# cooldrv.net
KiCad netlist of a schematic drawn in EAGLE
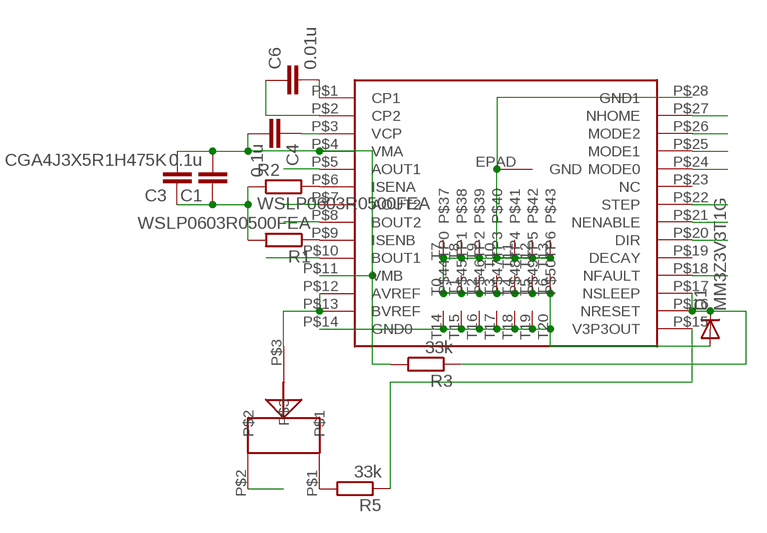
[diagram p0: schematic, sheet 1]

(export (version "E")
  (design (tool "Eeschema 10.0.6"))
  (components
    (comp (ref "C1")
      (value "0.1u")
      (footprint "eagle-import:C0603")
      (libsource (lib "eagle-import") (part "C-EUC0603"))
    )
    (comp (ref "C3")
      (value "CGA4J3X5R1H475K")
      (footprint "eagle-import:C0805K")
      (libsource (lib "eagle-import") (part "C-EUC0805K"))
    )
    (comp (ref "C4")
      (value "0.1u")
      (footprint "eagle-import:C0603K")
      (libsource (lib "eagle-import") (part "C-EUC0603K"))
    )
    (comp (ref "C6")
      (value "0.01u")
      (footprint "eagle-import:C0603")
      (libsource (lib "eagle-import") (part "C-EUC0603"))
    )
    (comp (ref "D1")
      (value "MM3Z3V3T1G")
      (footprint "eagle-import:SOD323-R")
      (libsource (lib "eagle-import") (part "DIODE-SOD323-R"))
    )
    (comp (ref "R1")
      (value "WSLP0603R0500FEA")
      (footprint "eagle-import:0805C")
      (libsource (lib "eagle-import") (part "0805CS"))
    )
    (comp (ref "R2")
      (value "WSLP0603R0500FEA")
      (footprint "eagle-import:0805C")
      (libsource (lib "eagle-import") (part "0805CS"))
    )
    (comp (ref "R3")
      (value "33k")
      (footprint "eagle-import:R0603")
      (libsource (lib "eagle-import") (part "R-EU_R0603"))
    )
    (comp (ref "R5")
      (value "33k")
      (footprint "eagle-import:R0603")
      (libsource (lib "eagle-import") (part "R-EU_R0603"))
    )
    (comp (ref "U$1")
      (value "DRV8825")
      (footprint "eagle-import:ETSSOP28")
      (libsource (lib "eagle-import") (part "DRV8825"))
    )
    (comp (ref "U$2")
      (value "EVM-3YSX50B14")
      (footprint "eagle-import:TRIMMER3MM")
      (libsource (lib "eagle-import") (part "TRIMMER3MM"))
    )
  )
  (nets
    (net (code "1") (name "/GND") (class "Default")
      (node (ref "C1") (pin "1") (pinfunction "1_1") (pintype "passive"))
      (node (ref "C3") (pin "1") (pinfunction "1_1") (pintype "passive"))
      (node (ref "D1") (pin "A") (pinfunction "A_A") (pintype "passive"))
      (node (ref "R1") (pin "2") (pinfunction "2_2") (pintype "passive"))
      (node (ref "R2") (pin "1") (pinfunction "1_1") (pintype "passive"))
      (node (ref "U$1") (pin "EPAD") (pinfunction "GND_EPAD") (pintype "bidirectional"))
      (node (ref "U$1") (pin "P$14") (pinfunction "GND0_P$14") (pintype "bidirectional"))
      (node (ref "U$1") (pin "P$28") (pinfunction "GND1_P$28") (pintype "bidirectional"))
      (node (ref "U$1") (pin "T0") (pinfunction "TP0_T0") (pintype "bidirectional"))
      (node (ref "U$1") (pin "T1") (pinfunction "TP1_T1") (pintype "bidirectional"))
      (node (ref "U$1") (pin "T10") (pinfunction "P$40_T10") (pintype "bidirectional"))
      (node (ref "U$1") (pin "T11") (pinfunction "P$41_T11") (pintype "bidirectional"))
      (node (ref "U$1") (pin "T12") (pinfunction "P$42_T12") (pintype "bidirectional"))
      (node (ref "U$1") (pin "T13") (pinfunction "P$43_T13") (pintype "bidirectional"))
      (node (ref "U$1") (pin "T14") (pinfunction "P$44_T14") (pintype "bidirectional"))
      (node (ref "U$1") (pin "T15") (pinfunction "P$45_T15") (pintype "bidirectional"))
      (node (ref "U$1") (pin "T16") (pinfunction "P$46_T16") (pintype "bidirectional"))
      (node (ref "U$1") (pin "T17") (pinfunction "P$47_T17") (pintype "bidirectional"))
      (node (ref "U$1") (pin "T18") (pinfunction "P$48_T18") (pintype "bidirectional"))
      (node (ref "U$1") (pin "T19") (pinfunction "P$49_T19") (pintype "bidirectional"))
      (node (ref "U$1") (pin "T2") (pinfunction "TP2_T2") (pintype "bidirectional"))
      (node (ref "U$1") (pin "T20") (pinfunction "P$50_T20") (pintype "bidirectional"))
      (node (ref "U$1") (pin "T3") (pinfunction "TP3_T3") (pintype "bidirectional"))
      (node (ref "U$1") (pin "T4") (pinfunction "TP4_T4") (pintype "bidirectional"))
      (node (ref "U$1") (pin "T5") (pinfunction "TP5_T5") (pintype "bidirectional"))
      (node (ref "U$1") (pin "T6") (pinfunction "TP6_T6") (pintype "bidirectional"))
      (node (ref "U$1") (pin "T7") (pinfunction "P$37_T7") (pintype "bidirectional"))
      (node (ref "U$1") (pin "T8") (pinfunction "P$38_T8") (pintype "bidirectional"))
      (node (ref "U$1") (pin "T9") (pinfunction "P$39_T9") (pintype "bidirectional"))
      (node (ref "U$2") (pin "P$2") (pinfunction "P$2_P$2") (pintype "bidirectional"))
    )
    (net (code "2") (name "Net-(R5-Pad2)") (class "Default")
      (node (ref "R5") (pin "2") (pinfunction "2_2") (pintype "passive"))
      (node (ref "U$2") (pin "P$1") (pinfunction "P$1_P$1") (pintype "bidirectional"))
    )
    (net (code "3") (name "Net-(U$1-AVREF)") (class "Default")
      (node (ref "U$1") (pin "P$12") (pinfunction "AVREF_P$12") (pintype "bidirectional"))
      (node (ref "U$1") (pin "P$13") (pinfunction "BVREF_P$13") (pintype "bidirectional"))
      (node (ref "U$2") (pin "P$3") (pinfunction "P$3_P$3") (pintype "bidirectional"))
    )
    (net (code "4") (name "Net-(U$1-CP1)") (class "Default")
      (node (ref "C6") (pin "2") (pinfunction "2_2") (pintype "passive"))
      (node (ref "U$1") (pin "P$1") (pinfunction "CP1_P$1") (pintype "bidirectional"))
    )
    (net (code "5") (name "Net-(U$1-CP2)") (class "Default")
      (node (ref "C6") (pin "1") (pinfunction "1_1") (pintype "passive"))
      (node (ref "U$1") (pin "P$2") (pinfunction "CP2_P$2") (pintype "bidirectional"))
    )
    (net (code "6") (name "Net-(U$1-ISENA)") (class "Default")
      (node (ref "R2") (pin "2") (pinfunction "2_2") (pintype "passive"))
      (node (ref "U$1") (pin "P$6") (pinfunction "ISENA_P$6") (pintype "bidirectional"))
    )
    (net (code "7") (name "Net-(U$1-ISENB)") (class "Default")
      (node (ref "R1") (pin "1") (pinfunction "1_1") (pintype "passive"))
      (node (ref "U$1") (pin "P$9") (pinfunction "ISENB_P$9") (pintype "bidirectional"))
    )
    (net (code "8") (name "Net-(U$1-NRESET)") (class "Default")
      (node (ref "D1") (pin "C") (pinfunction "C_C") (pintype "passive"))
      (node (ref "R3") (pin "1") (pinfunction "1_1") (pintype "passive"))
      (node (ref "U$1") (pin "P$16") (pinfunction "NRESET_P$16") (pintype "bidirectional"))
      (node (ref "U$1") (pin "P$17") (pinfunction "NSLEEP_P$17") (pintype "bidirectional"))
    )
    (net (code "9") (name "Net-(U$1-V3P3OUT)") (class "Default")
      (node (ref "R5") (pin "1") (pinfunction "1_1") (pintype "passive"))
      (node (ref "U$1") (pin "P$15") (pinfunction "V3P3OUT_P$15") (pintype "bidirectional"))
    )
    (net (code "10") (name "Net-(U$1-VCP)") (class "Default")
      (node (ref "C4") (pin "1") (pinfunction "1_1") (pintype "passive"))
      (node (ref "U$1") (pin "P$3") (pinfunction "VCP_P$3") (pintype "bidirectional"))
    )
    (net (code "11") (name "Net-(U$1-VMA)") (class "Default")
      (node (ref "C1") (pin "2") (pinfunction "2_2") (pintype "passive"))
      (node (ref "C3") (pin "2") (pinfunction "2_2") (pintype "passive"))
      (node (ref "C4") (pin "2") (pinfunction "2_2") (pintype "passive"))
      (node (ref "R3") (pin "2") (pinfunction "2_2") (pintype "passive"))
      (node (ref "U$1") (pin "P$11") (pinfunction "VMB_P$11") (pintype "bidirectional"))
      (node (ref "U$1") (pin "P$4") (pinfunction "VMA_P$4") (pintype "bidirectional"))
    )
    (net (code "12") (name "unconnected-(U$1-AOUT1-PadP$5)") (class "Default")
      (node (ref "U$1") (pin "P$5") (pinfunction "AOUT1_P$5") (pintype "bidirectional"))
    )
    (net (code "13") (name "unconnected-(U$1-AOUT2-PadP$7)") (class "Default")
      (node (ref "U$1") (pin "P$7") (pinfunction "AOUT2_P$7") (pintype "bidirectional"))
    )
    (net (code "14") (name "unconnected-(U$1-BOUT1-PadP$10)") (class "Default")
      (node (ref "U$1") (pin "P$10") (pinfunction "BOUT1_P$10") (pintype "bidirectional"))
    )
    (net (code "15") (name "unconnected-(U$1-BOUT2-PadP$8)") (class "Default")
      (node (ref "U$1") (pin "P$8") (pinfunction "BOUT2_P$8") (pintype "bidirectional"))
    )
    (net (code "16") (name "unconnected-(U$1-DECAY-PadP$19)") (class "Default")
      (node (ref "U$1") (pin "P$19") (pinfunction "DECAY_P$19") (pintype "bidirectional"))
    )
    (net (code "17") (name "unconnected-(U$1-DIR-PadP$20)") (class "Default")
      (node (ref "U$1") (pin "P$20") (pinfunction "DIR_P$20") (pintype "bidirectional"))
    )
    (net (code "18") (name "unconnected-(U$1-MODE0-PadP$24)") (class "Default")
      (node (ref "U$1") (pin "P$24") (pinfunction "MODE0_P$24") (pintype "bidirectional"))
    )
    (net (code "19") (name "unconnected-(U$1-MODE1-PadP$25)") (class "Default")
      (node (ref "U$1") (pin "P$25") (pinfunction "MODE1_P$25") (pintype "bidirectional"))
    )
    (net (code "20") (name "unconnected-(U$1-MODE2-PadP$26)") (class "Default")
      (node (ref "U$1") (pin "P$26") (pinfunction "MODE2_P$26") (pintype "bidirectional"))
    )
    (net (code "21") (name "unconnected-(U$1-NC-PadP$23)") (class "Default")
      (node (ref "U$1") (pin "P$23") (pinfunction "NC_P$23") (pintype "bidirectional"))
    )
    (net (code "22") (name "unconnected-(U$1-NENABLE-PadP$21)") (class "Default")
      (node (ref "U$1") (pin "P$21") (pinfunction "NENABLE_P$21") (pintype "bidirectional"))
    )
    (net (code "23") (name "unconnected-(U$1-NFAULT-PadP$18)") (class "Default")
      (node (ref "U$1") (pin "P$18") (pinfunction "NFAULT_P$18") (pintype "bidirectional"))
    )
    (net (code "24") (name "unconnected-(U$1-NHOME-PadP$27)") (class "Default")
      (node (ref "U$1") (pin "P$27") (pinfunction "NHOME_P$27") (pintype "bidirectional"))
    )
    (net (code "25") (name "unconnected-(U$1-STEP-PadP$22)") (class "Default")
      (node (ref "U$1") (pin "P$22") (pinfunction "STEP_P$22") (pintype "bidirectional"))
    )
  )
)
